# BLE.net
KiCad netlist of a schematic drawn in Altium Designer
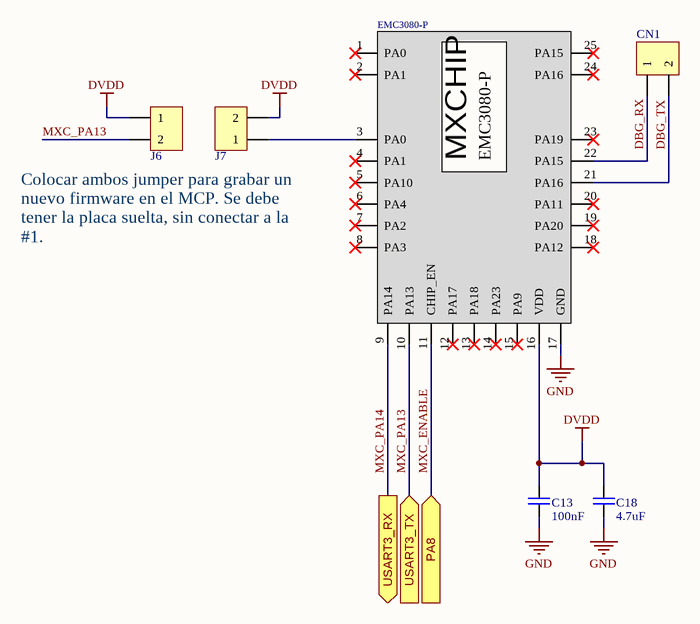
[diagram p0: BLE.SchDoc]

(export (version "E")
  (design (tool "Eeschema 10.0.6"))
  (components
    (comp (ref "C13")
      (value "100nF")
      (footprint "CAP_SM0805_YAGEOCC2_N")
      (description "CAP 100nF SM0805 X7R 25V YAGEO CC2")
      (fields
        (field (name "MANUFACTURER") "Yageo")
        (field (name "MANUFACTURER PART NUMBER") "CC0805KRX7R8BB104")
      )
      (libsource (lib "Yageo") (part "CC0805KRX7R8BB104"))
    )
    (comp (ref "C18")
      (value "4.7uF")
      (footprint "CAP_SM0805_YAGEOCC2_N")
      (description "CAP 4.7uF SM0805 X5R 10V YAGEO CC2")
      (fields
        (field (name "MANUFACTURER") "Yageo")
        (field (name "MANUFACTURER PART NUMBER") "CC0805KRX5R6BB475")
      )
      (libsource (lib "Yageo") (part "CC0805KRX5R6BB475"))
    )
    (comp (ref "CN1")
      (value "Usar Equivalente")
      (footprint "HEADER PIN 1X2")
      (description "1 x 2 - true hole  2.54mm - Pb free")
      (fields
        (field (name "MANUFACTURER") "Amphenol ICC")
        (field (name "MANUFACTURER PART NUMBER") "54101-T0602LF")
      )
      (libsource (lib "") (part "54101-T0602LF_1"))
    )
    (comp (ref "EMC3080-P")
      (value "EMC3080-P")
      (footprint "EMC3080-P")
      (description "Solamente es el zocalo donde va montado el chip, por eso no tiene modelo 3D")
      (fields (field (name "MANUFACTURER") "MXCHIP"))
      (libsource (lib "Microcontroladores") (part "EMC3080-P"))
    )
    (comp (ref "J6")
      (value "Usar Equivalente")
      (footprint "HEADER PIN 1X2")
      (description "1 x 2 - true hole  2.54mm - Pb free")
      (fields
        (field (name "MANUFACTURER") "Amphenol ICC")
        (field (name "MANUFACTURER PART NUMBER") "54101-T0602LF")
      )
      (libsource (lib "header_pin") (part "54101-T0602LF"))
    )
    (comp (ref "J7")
      (value "Usar Equivalente")
      (footprint "HEADER PIN 1X2")
      (description "1 x 2 - true hole  2.54mm - Pb free")
      (fields
        (field (name "MANUFACTURER") "Amphenol ICC")
        (field (name "MANUFACTURER PART NUMBER") "54101-T0602LF")
      )
      (libsource (lib "") (part "54101-T0602LF_2"))
    )
  )
  (nets
    (net (code "1") (name "/DBG_RX") (class "Default")
      (node (ref "CN1") (pin "1") (pinfunction "1_1") (pintype "passive"))
      (node (ref "EMC3080-P") (pin "22") (pinfunction "PA15_22") (pintype "passive"))
    )
    (net (code "2") (name "/DBG_TX") (class "Default")
      (node (ref "CN1") (pin "2") (pinfunction "2_2") (pintype "passive"))
      (node (ref "EMC3080-P") (pin "21") (pinfunction "PA16_21") (pintype "passive"))
    )
    (net (code "3") (name "/MXC_ENABLE") (class "Default")
      (node (ref "EMC3080-P") (pin "11") (pinfunction "CHIP_EN_11") (pintype "passive"))
    )
    (net (code "4") (name "/MXC_PA13") (class "Default")
      (node (ref "EMC3080-P") (pin "10") (pinfunction "PA13_10") (pintype "passive"))
      (node (ref "J6") (pin "2") (pinfunction "2_2") (pintype "passive"))
    )
    (net (code "5") (name "/MXC_PA14") (class "Default")
      (node (ref "EMC3080-P") (pin "9") (pinfunction "PA14_9") (pintype "passive"))
    )
    (net (code "6") (name "DVDD") (class "Default")
      (node (ref "C13") (pin "1") (pintype "passive"))
      (node (ref "C18") (pin "1") (pintype "passive"))
      (node (ref "EMC3080-P") (pin "16") (pinfunction "VDD_16") (pintype "passive"))
      (node (ref "J6") (pin "1") (pinfunction "1_1") (pintype "passive"))
      (node (ref "J7") (pin "2") (pinfunction "2_2") (pintype "passive"))
    )
    (net (code "7") (name "GND") (class "Default")
      (node (ref "C13") (pin "2") (pintype "passive"))
      (node (ref "C18") (pin "2") (pintype "passive"))
      (node (ref "EMC3080-P") (pin "17") (pinfunction "GND_17") (pintype "passive"))
    )
    (net (code "8") (name "Net-(EMC3080-P-PA0-Pad3)") (class "Default")
      (node (ref "EMC3080-P") (pin "3") (pinfunction "PA0_3") (pintype "passive"))
      (node (ref "J7") (pin "1") (pinfunction "1_1") (pintype "passive"))
    )
    (net (code "9") (name "unconnected-(EMC3080-P-PA0-Pad1)") (class "Default")
      (node (ref "EMC3080-P") (pin "1") (pinfunction "PA0_1") (pintype "passive+no_connect"))
    )
    (net (code "10") (name "unconnected-(EMC3080-P-PA1-Pad2)") (class "Default")
      (node (ref "EMC3080-P") (pin "2") (pinfunction "PA1_2") (pintype "passive+no_connect"))
    )
    (net (code "11") (name "unconnected-(EMC3080-P-PA1-Pad4)") (class "Default")
      (node (ref "EMC3080-P") (pin "4") (pinfunction "PA1_4") (pintype "passive+no_connect"))
    )
    (net (code "12") (name "unconnected-(EMC3080-P-PA2-Pad7)") (class "Default")
      (node (ref "EMC3080-P") (pin "7") (pinfunction "PA2_7") (pintype "passive+no_connect"))
    )
    (net (code "13") (name "unconnected-(EMC3080-P-PA3-Pad8)") (class "Default")
      (node (ref "EMC3080-P") (pin "8") (pinfunction "PA3_8") (pintype "passive+no_connect"))
    )
    (net (code "14") (name "unconnected-(EMC3080-P-PA4-Pad6)") (class "Default")
      (node (ref "EMC3080-P") (pin "6") (pinfunction "PA4_6") (pintype "passive+no_connect"))
    )
    (net (code "15") (name "unconnected-(EMC3080-P-PA9-Pad15)") (class "Default")
      (node (ref "EMC3080-P") (pin "15") (pinfunction "PA9_15") (pintype "passive+no_connect"))
    )
    (net (code "16") (name "unconnected-(EMC3080-P-PA10-Pad5)") (class "Default")
      (node (ref "EMC3080-P") (pin "5") (pinfunction "PA10_5") (pintype "passive+no_connect"))
    )
    (net (code "17") (name "unconnected-(EMC3080-P-PA11-Pad20)") (class "Default")
      (node (ref "EMC3080-P") (pin "20") (pinfunction "PA11_20") (pintype "passive+no_connect"))
    )
    (net (code "18") (name "unconnected-(EMC3080-P-PA12-Pad18)") (class "Default")
      (node (ref "EMC3080-P") (pin "18") (pinfunction "PA12_18") (pintype "passive+no_connect"))
    )
    (net (code "19") (name "unconnected-(EMC3080-P-PA15-Pad25)") (class "Default")
      (node (ref "EMC3080-P") (pin "25") (pinfunction "PA15_25") (pintype "passive+no_connect"))
    )
    (net (code "20") (name "unconnected-(EMC3080-P-PA16-Pad24)") (class "Default")
      (node (ref "EMC3080-P") (pin "24") (pinfunction "PA16_24") (pintype "passive+no_connect"))
    )
    (net (code "21") (name "unconnected-(EMC3080-P-PA17-Pad12)") (class "Default")
      (node (ref "EMC3080-P") (pin "12") (pinfunction "PA17_12") (pintype "passive+no_connect"))
    )
    (net (code "22") (name "unconnected-(EMC3080-P-PA18-Pad13)") (class "Default")
      (node (ref "EMC3080-P") (pin "13") (pinfunction "PA18_13") (pintype "passive+no_connect"))
    )
    (net (code "23") (name "unconnected-(EMC3080-P-PA19-Pad23)") (class "Default")
      (node (ref "EMC3080-P") (pin "23") (pinfunction "PA19_23") (pintype "passive+no_connect"))
    )
    (net (code "24") (name "unconnected-(EMC3080-P-PA20-Pad19)") (class "Default")
      (node (ref "EMC3080-P") (pin "19") (pinfunction "PA20_19") (pintype "passive+no_connect"))
    )
    (net (code "25") (name "unconnected-(EMC3080-P-PA23-Pad14)") (class "Default")
      (node (ref "EMC3080-P") (pin "14") (pinfunction "PA23_14") (pintype "passive+no_connect"))
    )
  )
)
